# design.net
KiCad netlist of a schematic drawn in Altium Designer
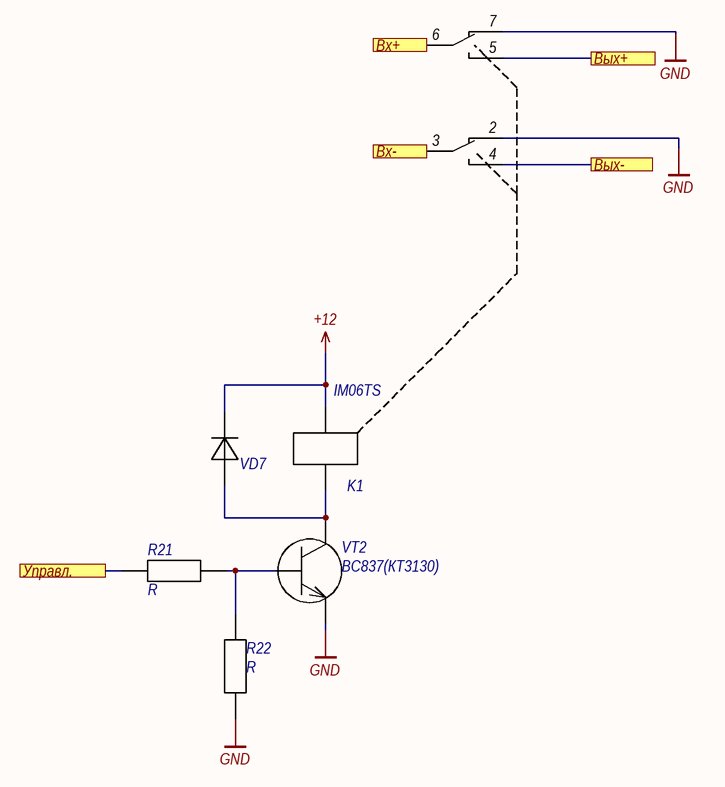
[diagram p0: РЕЛЕ.SchDoc]

(export (version "E")
  (design (tool "Eeschema 10.0.6"))
  (components
    (comp (ref "K1") (value "IM06TS") (footprint "IM06TS") (libsource (lib "UGO") (part "IM06TS")))
    (comp (ref "R21") (value "R") (footprint "R") (libsource (lib "UGO") (part "R")))
    (comp (ref "R22") (value "R") (footprint "R") (libsource (lib "") (part "R_1")))
    (comp (ref "VD7") (value "SS14") (footprint "SS14") (libsource (lib "UGO") (part "SS14")))
    (comp (ref "VT2")
      (value "BC837(КТ3130)")
      (footprint "BC847(IRLML6402)")
      (libsource (lib "UGO") (part "BC837(КТ3130)"))
    )
  )
  (nets
    (net (code "1") (name "+12") (class "Default")
      (node (ref "K1") (pin "1") (pintype "passive"))
      (node (ref "VD7") (pin "1") (pintype "passive"))
    )
    (net (code "2") (name "/Вх+") (class "Default") (node (ref "K1") (pin "6") (pintype "passive")))
    (net (code "3") (name "/Вх-") (class "Default") (node (ref "K1") (pin "3") (pintype "passive")))
    (net (code "4") (name "/Вых+") (class "Default") (node (ref "K1") (pin "5") (pintype "passive")))
    (net (code "5") (name "/Вых-") (class "Default") (node (ref "K1") (pin "4") (pintype "passive")))
    (net (code "6") (name "/Управл.") (class "Default") (node (ref "R21") (pin "1") (pintype "passive")))
    (net (code "7") (name "GND") (class "Default")
      (node (ref "K1") (pin "2") (pintype "passive"))
      (node (ref "K1") (pin "7") (pintype "passive"))
      (node (ref "R22") (pin "1") (pintype "passive"))
      (node (ref "VT2") (pin "2") (pintype "passive"))
    )
    (net (code "8") (name "Net-(K1-Pad8)") (class "Default")
      (node (ref "K1") (pin "8") (pintype "passive"))
      (node (ref "VD7") (pin "2") (pintype "passive"))
      (node (ref "VT2") (pin "3") (pintype "passive"))
    )
    (net (code "9") (name "Net-(R21-Pad2)") (class "Default")
      (node (ref "R21") (pin "2") (pintype "passive"))
      (node (ref "R22") (pin "2") (pintype "passive"))
      (node (ref "VT2") (pin "1") (pintype "passive"))
    )
  )
)
